# 24V_Multiphase_Buck.net
KiCad netlist of a schematic drawn in Altium Designer
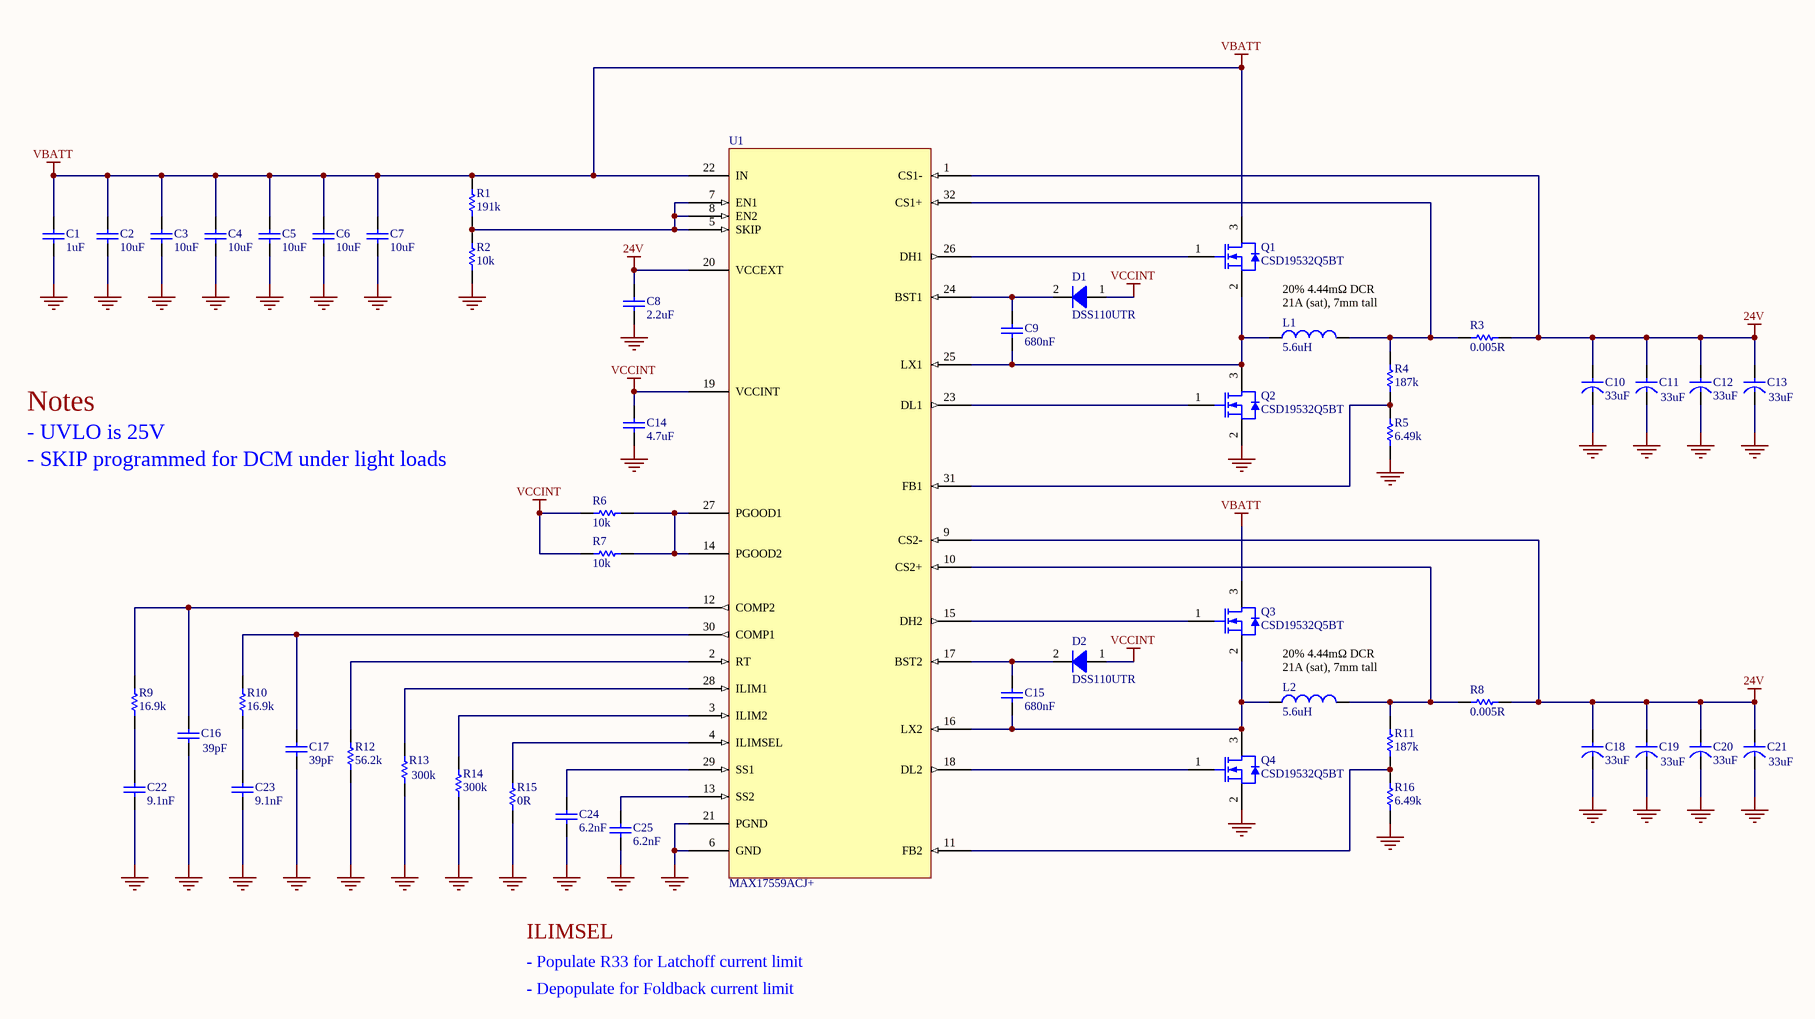
[diagram p0: 24V Multiphase Buck.SchDoc]

(export (version "E")
  (design (tool "Eeschema 10.0.6"))
  (components
    (comp (ref "C1")
      (value "1uF")
      (footprint "C1206")
      (description "Cap Ceramic 1uF 100V X7R 10% SMD 1206 125°C Embossed Plastic T/R")
      (fields (field (name "PART NUMBER") "CL31B105KCHNFNE") (field (name "MANUFACTURER") "Samsung"))
      (libsource (lib "EMRLibrary") (part "EMR_Cap"))
    )
    (comp (ref "C2")
      (value "10uF")
      (footprint "C2220")
      (description "Cap Ceramic 10uF 100V X7R 20% SMD 2220 125°C Embossed T/R")
      (fields (field (name "PART NUMBER") "22201C106MAT2A") (field (name "MANUFACTURER") "Kyocera AVX"))
      (libsource (lib "EMRLibrary") (part "EMR_Cap"))
    )
    (comp (ref "C3")
      (value "10uF")
      (footprint "C2220")
      (description "Cap Ceramic 10uF 100V X7R 20% SMD 2220 125°C Embossed T/R")
      (fields (field (name "PART NUMBER") "22201C106MAT2A") (field (name "MANUFACTURER") "Kyocera AVX"))
      (libsource (lib "EMRLibrary") (part "EMR_Cap"))
    )
    (comp (ref "C4")
      (value "10uF")
      (footprint "C2220")
      (description "Cap Ceramic 10uF 100V X7R 20% SMD 2220 125°C Embossed T/R")
      (fields (field (name "PART NUMBER") "22201C106MAT2A") (field (name "MANUFACTURER") "Kyocera AVX"))
      (libsource (lib "EMRLibrary") (part "EMR_Cap"))
    )
    (comp (ref "C5")
      (value "10uF")
      (footprint "C2220")
      (description "Cap Ceramic 10uF 100V X7R 20% SMD 2220 125°C Embossed T/R")
      (fields (field (name "PART NUMBER") "22201C106MAT2A") (field (name "MANUFACTURER") "Kyocera AVX"))
      (libsource (lib "EMRLibrary") (part "EMR_Cap"))
    )
    (comp (ref "C6")
      (value "10uF")
      (footprint "C2220")
      (description "Cap Ceramic 10uF 100V X7R 20% SMD 2220 125°C Embossed T/R")
      (fields (field (name "PART NUMBER") "22201C106MAT2A") (field (name "MANUFACTURER") "Kyocera AVX"))
      (libsource (lib "EMRLibrary") (part "EMR_Cap"))
    )
    (comp (ref "C7")
      (value "10uF")
      (footprint "C2220")
      (description "Cap Ceramic 10uF 100V X7R 20% SMD 2220 125°C Embossed T/R")
      (fields (field (name "PART NUMBER") "22201C106MAT2A") (field (name "MANUFACTURER") "Kyocera AVX"))
      (libsource (lib "EMRLibrary") (part "EMR_Cap"))
    )
    (comp (ref "C8")
      (value "2.2uF")
      (footprint "C0603")
      (description "0603 2.2 uF 50 V ±10 % Tolerance X5R SMT Multilayer Ceramic Capacitor")
      (fields (field (name "PART NUMBER") "GRT188R61H225KE13D") (field (name "MANUFACTURER") "Murata"))
      (libsource (lib "EMRLibrary") (part "EMR_Cap"))
    )
    (comp (ref "C9")
      (value "680nF")
      (footprint "C1206")
      (description "Cap Cer 0.68UF 100V X7R 1206")
      (fields (field (name "PART NUMBER") "C1206C684K1RAC7800") (field (name "MANUFACTURER") "KEMET"))
      (libsource (lib "EMRLibrary") (part "EMR_Cap"))
    )
    (comp (ref "C10")
      (value "33uF")
      (footprint "CAPAE9983X105M")
      (description "Cap 33UF 50V Elect Fc SMD")
      (fields (field (name "PART NUMBER") "EEV-FC1H330P") (field (name "MANUFACTURER") "Panasonic"))
      (libsource (lib "EMRLibrary") (part "EMR_Electro_Cap"))
    )
    (comp (ref "C11")
      (value "33uF")
      (footprint "CAPAE9983X105M")
      (description "Cap 33UF 50V Elect Fc SMD")
      (fields (field (name "PART NUMBER") "EEV-FC1H330P") (field (name "MANUFACTURER") "Panasonic"))
      (libsource (lib "EMRLibrary") (part "EMR_Electro_Cap"))
    )
    (comp (ref "C12")
      (value "33uF")
      (footprint "CAPAE9983X105M")
      (description "Cap 33UF 50V Elect Fc SMD")
      (fields (field (name "PART NUMBER") "EEV-FC1H330P") (field (name "MANUFACTURER") "Panasonic"))
      (libsource (lib "EMRLibrary") (part "EMR_Electro_Cap"))
    )
    (comp (ref "C13")
      (value "33uF")
      (footprint "CAPAE9983X105M")
      (description "Cap 33UF 50V Elect Fc SMD")
      (fields (field (name "PART NUMBER") "EEV-FC1H330P") (field (name "MANUFACTURER") "Panasonic"))
      (libsource (lib "EMRLibrary") (part "EMR_Electro_Cap"))
    )
    (comp (ref "C14")
      (value "4.7uF")
      (footprint "C0805")
      (description "4.7µF Ceramic Capacitor 16V % Samsung Electro-Mechanics CL21A475KOFNNNG")
      (fields (field (name "PART NUMBER") "CL21A475KOFNNNG") (field (name "MANUFACTURER") "Samsung"))
      (libsource (lib "EMRLibrary") (part "EMR_Cap"))
    )
    (comp (ref "C15")
      (value "680nF")
      (footprint "C1206")
      (description "Cap Cer 0.68UF 100V X7R 1206")
      (fields (field (name "PART NUMBER") "C1206C684K1RAC7800") (field (name "MANUFACTURER") "KEMET"))
      (libsource (lib "EMRLibrary") (part "EMR_Cap"))
    )
    (comp (ref "C16")
      (value "39pF")
      (footprint "C0805")
      (description "Ceramic capacitor SMD-0805 39pF /50V NP0# J +-5% Samsung , RoHS")
      (fields (field (name "PART NUMBER") "CL21C390JBANNNC") (field (name "MANUFACTURER") "Samsung"))
      (libsource (lib "") (part "EMR_Cap_1"))
    )
    (comp (ref "C17")
      (value "39pF")
      (footprint "C0805")
      (description "Ceramic capacitor SMD-0805 39pF /50V NP0# J +-5% Samsung , RoHS")
      (fields (field (name "PART NUMBER") "CL21C390JBANNNC") (field (name "MANUFACTURER") "Samsung"))
      (libsource (lib "") (part "EMR_Cap_1"))
    )
    (comp (ref "C18")
      (value "33uF")
      (footprint "CAPAE9983X105M")
      (description "Cap 33UF 50V Elect Fc SMD")
      (fields (field (name "PART NUMBER") "EEV-FC1H330P") (field (name "MANUFACTURER") "Panasonic"))
      (libsource (lib "EMRLibrary") (part "EMR_Electro_Cap"))
    )
    (comp (ref "C19")
      (value "33uF")
      (footprint "CAPAE9983X105M")
      (description "Cap 33UF 50V Elect Fc SMD")
      (fields (field (name "PART NUMBER") "EEV-FC1H330P") (field (name "MANUFACTURER") "Panasonic"))
      (libsource (lib "EMRLibrary") (part "EMR_Electro_Cap"))
    )
    (comp (ref "C20")
      (value "33uF")
      (footprint "CAPAE9983X105M")
      (description "Cap 33UF 50V Elect Fc SMD")
      (fields (field (name "PART NUMBER") "EEV-FC1H330P") (field (name "MANUFACTURER") "Panasonic"))
      (libsource (lib "EMRLibrary") (part "EMR_Electro_Cap"))
    )
    (comp (ref "C21")
      (value "33uF")
      (footprint "CAPAE9983X105M")
      (description "Cap 33UF 50V Elect Fc SMD")
      (fields (field (name "PART NUMBER") "EEV-FC1H330P") (field (name "MANUFACTURER") "Panasonic"))
      (libsource (lib "EMRLibrary") (part "EMR_Electro_Cap"))
    )
    (comp (ref "C22")
      (value "9.1nF")
      (footprint "C0603")
      (description "Cap Ceramic 0.0091uF 25V C0G 5% Pad SMD 0603 125°C Extreme Low ESR T/R")
      (fields (field (name "PART NUMBER") "C0603C912J3GACTU") (field (name "MANUFACTURER") "KEMET"))
      (libsource (lib "EMRLibrary") (part "EMR_Cap"))
    )
    (comp (ref "C23")
      (value "9.1nF")
      (footprint "C0603")
      (description "Cap Ceramic 0.0091uF 25V C0G 5% Pad SMD 0603 125°C Extreme Low ESR T/R")
      (fields (field (name "PART NUMBER") "C0603C912J3GACTU") (field (name "MANUFACTURER") "KEMET"))
      (libsource (lib "EMRLibrary") (part "EMR_Cap"))
    )
    (comp (ref "C24")
      (value "6.2nF")
      (footprint "C0603")
      (description "Cap MLCC SMD 0603 100V X7R 6200pF ±5% Commercial Ti/Sn Plated 7T/R\"")
      (fields (field (name "PART NUMBER") "06031C622JAT2A") (field (name "MANUFACTURER") "Kyocera AVX"))
      (libsource (lib "EMRLibrary") (part "EMR_Cap"))
    )
    (comp (ref "C25")
      (value "6.2nF")
      (footprint "C0603")
      (description "Cap MLCC SMD 0603 100V X7R 6200pF ±5% Commercial Ti/Sn Plated 7T/R\"")
      (fields (field (name "PART NUMBER") "06031C622JAT2A") (field (name "MANUFACTURER") "Kyocera AVX"))
      (libsource (lib "EMRLibrary") (part "EMR_Cap"))
    )
    (comp (ref "D1")
      (value "DSS110UTR")
      (footprint "SODFL360X110-2N")
      (description "Schottky 100V SOD-123FL")
      (fields (field (name "MANUFACTURER") "SMC"))
      (libsource (lib "EMRLibrary") (part "EMR_Diode"))
    )
    (comp (ref "D2")
      (value "DSS110UTR")
      (footprint "SODFL360X110-2N")
      (description "Schottky 100V SOD-123FL")
      (fields (field (name "MANUFACTURER") "SMC"))
      (libsource (lib "EMRLibrary") (part "EMR_Diode"))
    )
    (comp (ref "L1")
      (value "5.6uH")
      (footprint "IHLP6767GZER5R6M11")
      (description "Ind High Current Shielded Wirewound 5.6uH 20% 100KHz 28A 6767 T/R")
      (fields (field (name "PART NUMBER") "IHLP6767GZER5R6M11") (field (name "MANUFACTURER") "Vishay Dale"))
      (libsource (lib "EMRLibrary") (part "EMR_Inductor"))
    )
    (comp (ref "L2")
      (value "5.6uH")
      (footprint "IHLP6767GZER5R6M11")
      (description "Ind High Current Shielded Wirewound 5.6uH 20% 100KHz 28A 6767 T/R")
      (fields (field (name "PART NUMBER") "IHLP6767GZER5R6M11") (field (name "MANUFACTURER") "Vishay Dale"))
      (libsource (lib "EMRLibrary") (part "EMR_Inductor"))
    )
    (comp (ref "Q1")
      (value "CSD19532Q5BT")
      (footprint "CSD19532Q5BT")
      (description "MOSFET N-CH 100V 100A VSON")
      (fields (field (name "MANUFACTURER") "Texas Instruments"))
      (libsource (lib "EMRLibrary") (part "BSS138L"))
    )
    (comp (ref "Q2")
      (value "CSD19532Q5BT")
      (footprint "CSD19532Q5BT")
      (description "MOSFET N-CH 100V 100A VSON")
      (fields (field (name "MANUFACTURER") "Texas Instruments"))
      (libsource (lib "EMRLibrary") (part "BSS138L"))
    )
    (comp (ref "Q3")
      (value "CSD19532Q5BT")
      (footprint "CSD19532Q5BT")
      (description "MOSFET N-CH 100V 100A VSON")
      (fields (field (name "MANUFACTURER") "Texas Instruments"))
      (libsource (lib "EMRLibrary") (part "BSS138L"))
    )
    (comp (ref "Q4")
      (value "CSD19532Q5BT")
      (footprint "CSD19532Q5BT")
      (description "MOSFET N-CH 100V 100A VSON")
      (fields (field (name "MANUFACTURER") "Texas Instruments"))
      (libsource (lib "EMRLibrary") (part "BSS138L"))
    )
    (comp (ref "R1")
      (value "191k")
      (footprint "RESC1005X04N")
      (description "Res Thick Film 0402 191K Ohm 1% 1/16W 100ppm/C Molded SMD Paper T/R")
      (fields (field (name "PART NUMBER") "RC0402FR-07191KL") (field (name "MANUFACTURER") "Yageo"))
      (libsource (lib "EMRLibrary") (part "RC0402"))
    )
    (comp (ref "R2")
      (value "10k")
      (footprint "RESC1005X04N")
      (description "RES SMD 10K OHM 1% 1/16W 0402")
      (fields (field (name "PART NUMBER") "RC0402FR-0710KL") (field (name "MANUFACTURER") "Yageo"))
      (libsource (lib "EMRLibrary") (part "RC0402"))
    )
    (comp (ref "R3")
      (value "0.005R")
      (description "Res Metal Alloy 2728 0.005 Ohm 1% 4W ±25ppm/°C Molded SMD SMD Plastic T/R")
      (fields
        (field (name "PART NUMBER") "CSSH2728FT5L00")
        (field (name "MANUFACTURER") "Stackpole Electronics")
      )
      (libsource (lib "EMRLibrary") (part "RC0402"))
    )
    (comp (ref "R4")
      (value "187k")
      (footprint "RESC1005X04N")
      (description "Res Thick Film 1.0 x 0.5 mm 187K Ohm 1% 0.063W(1/16W) 100ppm/ C Molded SMD Paper T/R")
      (fields (field (name "PART NUMBER") "RC0402FR-07187KL") (field (name "MANUFACTURER") "Yageo"))
      (libsource (lib "EMRLibrary") (part "RC0402"))
    )
    (comp (ref "R5")
      (value "6.49k")
      (footprint "RESC1005X04N")
      (description "Chip Resistor Automotive Grade Thick Film 0402 6.49kOhm 1% Paper T/R")
      (fields (field (name "PART NUMBER") "AC0402FR-076K49L") (field (name "MANUFACTURER") "Yageo"))
      (libsource (lib "EMRLibrary") (part "RC0402"))
    )
    (comp (ref "R6")
      (value "10k")
      (footprint "RESC1005X04N")
      (description "RES SMD 10K OHM 1% 1/16W 0402")
      (fields (field (name "PART NUMBER") "RC0402FR-0710KL") (field (name "MANUFACTURER") "Yageo"))
      (libsource (lib "EMRLibrary") (part "RC0402"))
    )
    (comp (ref "R7")
      (value "10k")
      (footprint "RESC1005X04N")
      (description "RES SMD 10K OHM 1% 1/16W 0402")
      (fields (field (name "PART NUMBER") "RC0402FR-0710KL") (field (name "MANUFACTURER") "Yageo"))
      (libsource (lib "EMRLibrary") (part "RC0402"))
    )
    (comp (ref "R8")
      (value "0.005R")
      (description "Res Metal Alloy 2728 0.005 Ohm 1% 4W ±25ppm/°C Molded SMD SMD Plastic T/R")
      (fields
        (field (name "PART NUMBER") "CSSH2728FT5L00")
        (field (name "MANUFACTURER") "Stackpole Electronics")
      )
      (libsource (lib "EMRLibrary") (part "RC0402"))
    )
    (comp (ref "R9")
      (value "16.9k")
      (footprint "R0805")
      (description "Res Thick Film 0805 16.9K Ohm 1% 1/8W 100ppm/C Molded SMD SMD Paper T/R")
      (fields (field (name "PART NUMBER") "RC0805FR-0716K9L") (field (name "MANUFACTURER") "Yageo"))
      (libsource (lib "EMRLibrary") (part "RC0402"))
    )
    (comp (ref "R10")
      (value "16.9k")
      (footprint "R0805")
      (description "Res Thick Film 0805 16.9K Ohm 1% 1/8W 100ppm/C Molded SMD SMD Paper T/R")
      (fields (field (name "PART NUMBER") "RC0805FR-0716K9L") (field (name "MANUFACTURER") "Yageo"))
      (libsource (lib "EMRLibrary") (part "RC0402"))
    )
    (comp (ref "R11")
      (value "187k")
      (footprint "RESC1005X04N")
      (description "Res Thick Film 1.0 x 0.5 mm 187K Ohm 1% 0.063W(1/16W) 100ppm/ C Molded SMD Paper T/R")
      (fields (field (name "PART NUMBER") "RC0402FR-07187KL") (field (name "MANUFACTURER") "Yageo"))
      (libsource (lib "EMRLibrary") (part "RC0402"))
    )
    (comp (ref "R12")
      (value "56.2k")
      (footprint "RESC1005X04N")
      (description "Res General Purpose Thick Film 0402 56.2K Ohm 1% 1/16W ±100ppm/°C Molded SMD Paper T/R")
      (fields (field (name "PART NUMBER") "RC0402FR-0756K2L") (field (name "MANUFACTURER") "Yageo"))
      (libsource (lib "EMRLibrary") (part "RC0402"))
    )
    (comp (ref "R13")
      (value "300k")
      (footprint "RESC1005X04N")
      (fields
        (field (name "PART NUMBER") "RC0402FR-07300KL")
        (field (name "MANUFACTURER") "Yageo")
        (field (name "TOLERANCE") "1%")
      )
      (libsource (lib "EMRLibrary") (part "RC0402"))
    )
    (comp (ref "R14")
      (value "300k")
      (footprint "RESC1005X04N")
      (fields
        (field (name "PART NUMBER") "RC0402FR-07300KL")
        (field (name "MANUFACTURER") "Yageo")
        (field (name "TOLERANCE") "1%")
      )
      (libsource (lib "EMRLibrary") (part "RC0402"))
    )
    (comp (ref "R15")
      (value "0R")
      (footprint "RESC1005X04N")
      (description "Thick Film Resistors - SMD 0.0ohm 1%")
      (fields (field (name "PART NUMBER") "RC0402FR-070RL") (field (name "MANUFACTURER") "Yageo"))
      (libsource (lib "EMRLibrary") (part "RC0402"))
    )
    (comp (ref "R16")
      (value "6.49k")
      (footprint "RESC1005X04N")
      (description "Chip Resistor Automotive Grade Thick Film 0402 6.49kOhm 1% Paper T/R")
      (fields (field (name "PART NUMBER") "AC0402FR-076K49L") (field (name "MANUFACTURER") "Yageo"))
      (libsource (lib "EMRLibrary") (part "RC0402"))
    )
    (comp (ref "U1")
      (value "MAX17559ACJ+")
      (description "Buck Regulator Positive Output Step-Down - DC-DC Controller IC 32-TQFP (7x7)")
      (libsource (lib "EMR") (part "MAX17559ACJ+"))
    )
  )
  (nets
    (net (code "1") (name "24V") (class "Default")
      (node (ref "C10") (pin "1") (pinfunction "+_1") (pintype "passive"))
      (node (ref "C11") (pin "1") (pinfunction "+_1") (pintype "passive"))
      (node (ref "C12") (pin "1") (pinfunction "+_1") (pintype "passive"))
      (node (ref "C13") (pin "1") (pinfunction "+_1") (pintype "passive"))
      (node (ref "C18") (pin "1") (pinfunction "+_1") (pintype "passive"))
      (node (ref "C19") (pin "1") (pinfunction "+_1") (pintype "passive"))
      (node (ref "C20") (pin "1") (pinfunction "+_1") (pintype "passive"))
      (node (ref "C21") (pin "1") (pinfunction "+_1") (pintype "passive"))
      (node (ref "C8") (pin "2") (pinfunction "2_2") (pintype "passive"))
      (node (ref "R3") (pin "2") (pinfunction "2_2") (pintype "passive"))
      (node (ref "R8") (pin "2") (pinfunction "2_2") (pintype "passive"))
      (node (ref "U1") (pin "1") (pinfunction "CS1-_1") (pintype "input"))
      (node (ref "U1") (pin "20") (pinfunction "VCCEXT_20") (pintype "power_in"))
      (node (ref "U1") (pin "9") (pinfunction "CS2-_9") (pintype "input"))
    )
    (net (code "2") (name "GND") (class "Default")
      (node (ref "C1") (pin "1") (pinfunction "1_1") (pintype "passive"))
      (node (ref "C10") (pin "2") (pinfunction "-_2") (pintype "passive"))
      (node (ref "C11") (pin "2") (pinfunction "-_2") (pintype "passive"))
      (node (ref "C12") (pin "2") (pinfunction "-_2") (pintype "passive"))
      (node (ref "C13") (pin "2") (pinfunction "-_2") (pintype "passive"))
      (node (ref "C14") (pin "1") (pinfunction "1_1") (pintype "passive"))
      (node (ref "C16") (pin "1") (pinfunction "1_1") (pintype "passive"))
      (node (ref "C17") (pin "1") (pinfunction "1_1") (pintype "passive"))
      (node (ref "C18") (pin "2") (pinfunction "-_2") (pintype "passive"))
      (node (ref "C19") (pin "2") (pinfunction "-_2") (pintype "passive"))
      (node (ref "C2") (pin "1") (pinfunction "1_1") (pintype "passive"))
      (node (ref "C20") (pin "2") (pinfunction "-_2") (pintype "passive"))
      (node (ref "C21") (pin "2") (pinfunction "-_2") (pintype "passive"))
      (node (ref "C22") (pin "1") (pinfunction "1_1") (pintype "passive"))
      (node (ref "C23") (pin "1") (pinfunction "1_1") (pintype "passive"))
      (node (ref "C24") (pin "1") (pinfunction "1_1") (pintype "passive"))
      (node (ref "C25") (pin "1") (pinfunction "1_1") (pintype "passive"))
      (node (ref "C3") (pin "1") (pinfunction "1_1") (pintype "passive"))
      (node (ref "C4") (pin "1") (pinfunction "1_1") (pintype "passive"))
      (node (ref "C5") (pin "1") (pinfunction "1_1") (pintype "passive"))
      (node (ref "C6") (pin "1") (pinfunction "1_1") (pintype "passive"))
      (node (ref "C7") (pin "1") (pinfunction "1_1") (pintype "passive"))
      (node (ref "C8") (pin "1") (pinfunction "1_1") (pintype "passive"))
      (node (ref "Q2") (pin "2") (pinfunction "S_2") (pintype "passive"))
      (node (ref "Q4") (pin "2") (pinfunction "S_2") (pintype "passive"))
      (node (ref "R12") (pin "1") (pinfunction "1_1") (pintype "passive"))
      (node (ref "R13") (pin "1") (pinfunction "1_1") (pintype "passive"))
      (node (ref "R14") (pin "1") (pinfunction "1_1") (pintype "passive"))
      (node (ref "R15") (pin "1") (pinfunction "1_1") (pintype "passive"))
      (node (ref "R16") (pin "1") (pinfunction "1_1") (pintype "passive"))
      (node (ref "R2") (pin "1") (pinfunction "1_1") (pintype "passive"))
      (node (ref "R5") (pin "1") (pinfunction "1_1") (pintype "passive"))
      (node (ref "U1") (pin "21") (pinfunction "PGND_21") (pintype "power_in"))
      (node (ref "U1") (pin "6") (pinfunction "GND_6") (pintype "power_in"))
    )
    (net (code "3") (name "Net-(C22-Pad2)") (class "Default")
      (node (ref "C22") (pin "2") (pinfunction "2_2") (pintype "passive"))
      (node (ref "R9") (pin "1") (pinfunction "1_1") (pintype "passive"))
    )
    (net (code "4") (name "Net-(C23-Pad2)") (class "Default")
      (node (ref "C23") (pin "2") (pinfunction "2_2") (pintype "passive"))
      (node (ref "R10") (pin "1") (pinfunction "1_1") (pintype "passive"))
    )
    (net (code "5") (name "Net-(D1-K)") (class "Default")
      (node (ref "C9") (pin "2") (pinfunction "2_2") (pintype "passive"))
      (node (ref "D1") (pin "2") (pinfunction "K_2") (pintype "passive"))
      (node (ref "U1") (pin "24") (pinfunction "BST1_24") (pintype "input"))
    )
    (net (code "6") (name "Net-(D2-K)") (class "Default")
      (node (ref "C15") (pin "2") (pinfunction "2_2") (pintype "passive"))
      (node (ref "D2") (pin "2") (pinfunction "K_2") (pintype "passive"))
      (node (ref "U1") (pin "17") (pinfunction "BST2_17") (pintype "input"))
    )
    (net (code "7") (name "Net-(Q1-G)") (class "Default")
      (node (ref "Q1") (pin "1") (pinfunction "G_1") (pintype "passive"))
      (node (ref "U1") (pin "26") (pinfunction "DH1_26") (pintype "output"))
    )
    (net (code "8") (name "Net-(Q1-S)") (class "Default")
      (node (ref "C9") (pin "1") (pinfunction "1_1") (pintype "passive"))
      (node (ref "L1") (pin "1") (pinfunction "1_1") (pintype "passive"))
      (node (ref "Q1") (pin "2") (pinfunction "S_2") (pintype "passive"))
      (node (ref "Q2") (pin "3") (pinfunction "D_3") (pintype "passive"))
      (node (ref "U1") (pin "25") (pinfunction "LX1_25") (pintype "input"))
    )
    (net (code "9") (name "Net-(Q2-G)") (class "Default")
      (node (ref "Q2") (pin "1") (pinfunction "G_1") (pintype "passive"))
      (node (ref "U1") (pin "23") (pinfunction "DL1_23") (pintype "output"))
    )
    (net (code "10") (name "Net-(Q3-G)") (class "Default")
      (node (ref "Q3") (pin "1") (pinfunction "G_1") (pintype "passive"))
      (node (ref "U1") (pin "15") (pinfunction "DH2_15") (pintype "output"))
    )
    (net (code "11") (name "Net-(Q3-S)") (class "Default")
      (node (ref "C15") (pin "1") (pinfunction "1_1") (pintype "passive"))
      (node (ref "L2") (pin "1") (pinfunction "1_1") (pintype "passive"))
      (node (ref "Q3") (pin "2") (pinfunction "S_2") (pintype "passive"))
      (node (ref "Q4") (pin "3") (pinfunction "D_3") (pintype "passive"))
      (node (ref "U1") (pin "16") (pinfunction "LX2_16") (pintype "input"))
    )
    (net (code "12") (name "Net-(Q4-G)") (class "Default")
      (node (ref "Q4") (pin "1") (pinfunction "G_1") (pintype "passive"))
      (node (ref "U1") (pin "18") (pinfunction "DL2_18") (pintype "output"))
    )
    (net (code "13") (name "Net-(U1-COMP1)") (class "Default")
      (node (ref "C17") (pin "2") (pinfunction "2_2") (pintype "passive"))
      (node (ref "R10") (pin "2") (pinfunction "2_2") (pintype "passive"))
      (node (ref "U1") (pin "30") (pinfunction "COMP1_30") (pintype "output"))
    )
    (net (code "14") (name "Net-(U1-COMP2)") (class "Default")
      (node (ref "C16") (pin "2") (pinfunction "2_2") (pintype "passive"))
      (node (ref "R9") (pin "2") (pinfunction "2_2") (pintype "passive"))
      (node (ref "U1") (pin "12") (pinfunction "COMP2_12") (pintype "output"))
    )
    (net (code "15") (name "Net-(U1-CS1+)") (class "Default")
      (node (ref "L1") (pin "2") (pinfunction "2_2") (pintype "passive"))
      (node (ref "R3") (pin "1") (pinfunction "1_1") (pintype "passive"))
      (node (ref "R4") (pin "2") (pinfunction "2_2") (pintype "passive"))
      (node (ref "U1") (pin "32") (pinfunction "CS1+_32") (pintype "input"))
    )
    (net (code "16") (name "Net-(U1-CS2+)") (class "Default")
      (node (ref "L2") (pin "2") (pinfunction "2_2") (pintype "passive"))
      (node (ref "R11") (pin "2") (pinfunction "2_2") (pintype "passive"))
      (node (ref "R8") (pin "1") (pinfunction "1_1") (pintype "passive"))
      (node (ref "U1") (pin "10") (pinfunction "CS2+_10") (pintype "input"))
    )
    (net (code "17") (name "Net-(U1-EN1)") (class "Default")
      (node (ref "R1") (pin "1") (pinfunction "1_1") (pintype "passive"))
      (node (ref "R2") (pin "2") (pinfunction "2_2") (pintype "passive"))
      (node (ref "U1") (pin "5") (pinfunction "SKIP_5") (pintype "input"))
      (node (ref "U1") (pin "7") (pinfunction "EN1_7") (pintype "input"))
      (node (ref "U1") (pin "8") (pinfunction "EN2_8") (pintype "input"))
    )
    (net (code "18") (name "Net-(U1-FB1)") (class "Default")
      (node (ref "R4") (pin "1") (pinfunction "1_1") (pintype "passive"))
      (node (ref "R5") (pin "2") (pinfunction "2_2") (pintype "passive"))
      (node (ref "U1") (pin "31") (pinfunction "FB1_31") (pintype "input"))
    )
    (net (code "19") (name "Net-(U1-FB2)") (class "Default")
      (node (ref "R11") (pin "1") (pinfunction "1_1") (pintype "passive"))
      (node (ref "R16") (pin "2") (pinfunction "2_2") (pintype "passive"))
      (node (ref "U1") (pin "11") (pinfunction "FB2_11") (pintype "input"))
    )
    (net (code "20") (name "Net-(U1-ILIM1)") (class "Default")
      (node (ref "R13") (pin "2") (pinfunction "2_2") (pintype "passive"))
      (node (ref "U1") (pin "28") (pinfunction "ILIM1_28") (pintype "input"))
    )
    (net (code "21") (name "Net-(U1-ILIM2)") (class "Default")
      (node (ref "R14") (pin "2") (pinfunction "2_2") (pintype "passive"))
      (node (ref "U1") (pin "3") (pinfunction "ILIM2_3") (pintype "input"))
    )
    (net (code "22") (name "Net-(U1-ILIMSEL)") (class "Default")
      (node (ref "R15") (pin "2") (pinfunction "2_2") (pintype "passive"))
      (node (ref "U1") (pin "4") (pinfunction "ILIMSEL_4") (pintype "input"))
    )
    (net (code "23") (name "Net-(U1-PGOOD1)") (class "Default")
      (node (ref "R6") (pin "2") (pinfunction "2_2") (pintype "passive"))
      (node (ref "R7") (pin "2") (pinfunction "2_2") (pintype "passive"))
      (node (ref "U1") (pin "14") (pinfunction "PGOOD2_14") (pintype "open_collector"))
      (node (ref "U1") (pin "27") (pinfunction "PGOOD1_27") (pintype "open_collector"))
    )
    (net (code "24") (name "Net-(U1-RT)") (class "Default")
      (node (ref "R12") (pin "2") (pinfunction "2_2") (pintype "passive"))
      (node (ref "U1") (pin "2") (pinfunction "RT_2") (pintype "input"))
    )
    (net (code "25") (name "Net-(U1-SS1)") (class "Default")
      (node (ref "C24") (pin "2") (pinfunction "2_2") (pintype "passive"))
      (node (ref "U1") (pin "29") (pinfunction "SS1_29") (pintype "input"))
    )
    (net (code "26") (name "Net-(U1-SS2)") (class "Default")
      (node (ref "C25") (pin "2") (pinfunction "2_2") (pintype "passive"))
      (node (ref "U1") (pin "13") (pinfunction "SS2_13") (pintype "input"))
    )
    (net (code "27") (name "VBATT") (class "Default")
      (node (ref "C1") (pin "2") (pinfunction "2_2") (pintype "passive"))
      (node (ref "C2") (pin "2") (pinfunction "2_2") (pintype "passive"))
      (node (ref "C3") (pin "2") (pinfunction "2_2") (pintype "passive"))
      (node (ref "C4") (pin "2") (pinfunction "2_2") (pintype "passive"))
      (node (ref "C5") (pin "2") (pinfunction "2_2") (pintype "passive"))
      (node (ref "C6") (pin "2") (pinfunction "2_2") (pintype "passive"))
      (node (ref "C7") (pin "2") (pinfunction "2_2") (pintype "passive"))
      (node (ref "Q1") (pin "3") (pinfunction "D_3") (pintype "passive"))
      (node (ref "Q3") (pin "3") (pinfunction "D_3") (pintype "passive"))
      (node (ref "R1") (pin "2") (pinfunction "2_2") (pintype "passive"))
      (node (ref "U1") (pin "22") (pinfunction "IN_22") (pintype "power_in"))
    )
    (net (code "28") (name "VCCINT") (class "Default")
      (node (ref "C14") (pin "2") (pinfunction "2_2") (pintype "passive"))
      (node (ref "D1") (pin "1") (pinfunction "A_1") (pintype "passive"))
      (node (ref "D2") (pin "1") (pinfunction "A_1") (pintype "passive"))
      (node (ref "R6") (pin "1") (pinfunction "1_1") (pintype "passive"))
      (node (ref "R7") (pin "1") (pinfunction "1_1") (pintype "passive"))
      (node (ref "U1") (pin "19") (pinfunction "VCCINT_19") (pintype "power_in"))
    )
  )
)
